# uk_ad.net
KiCad netlist of a schematic drawn in Altium Designer
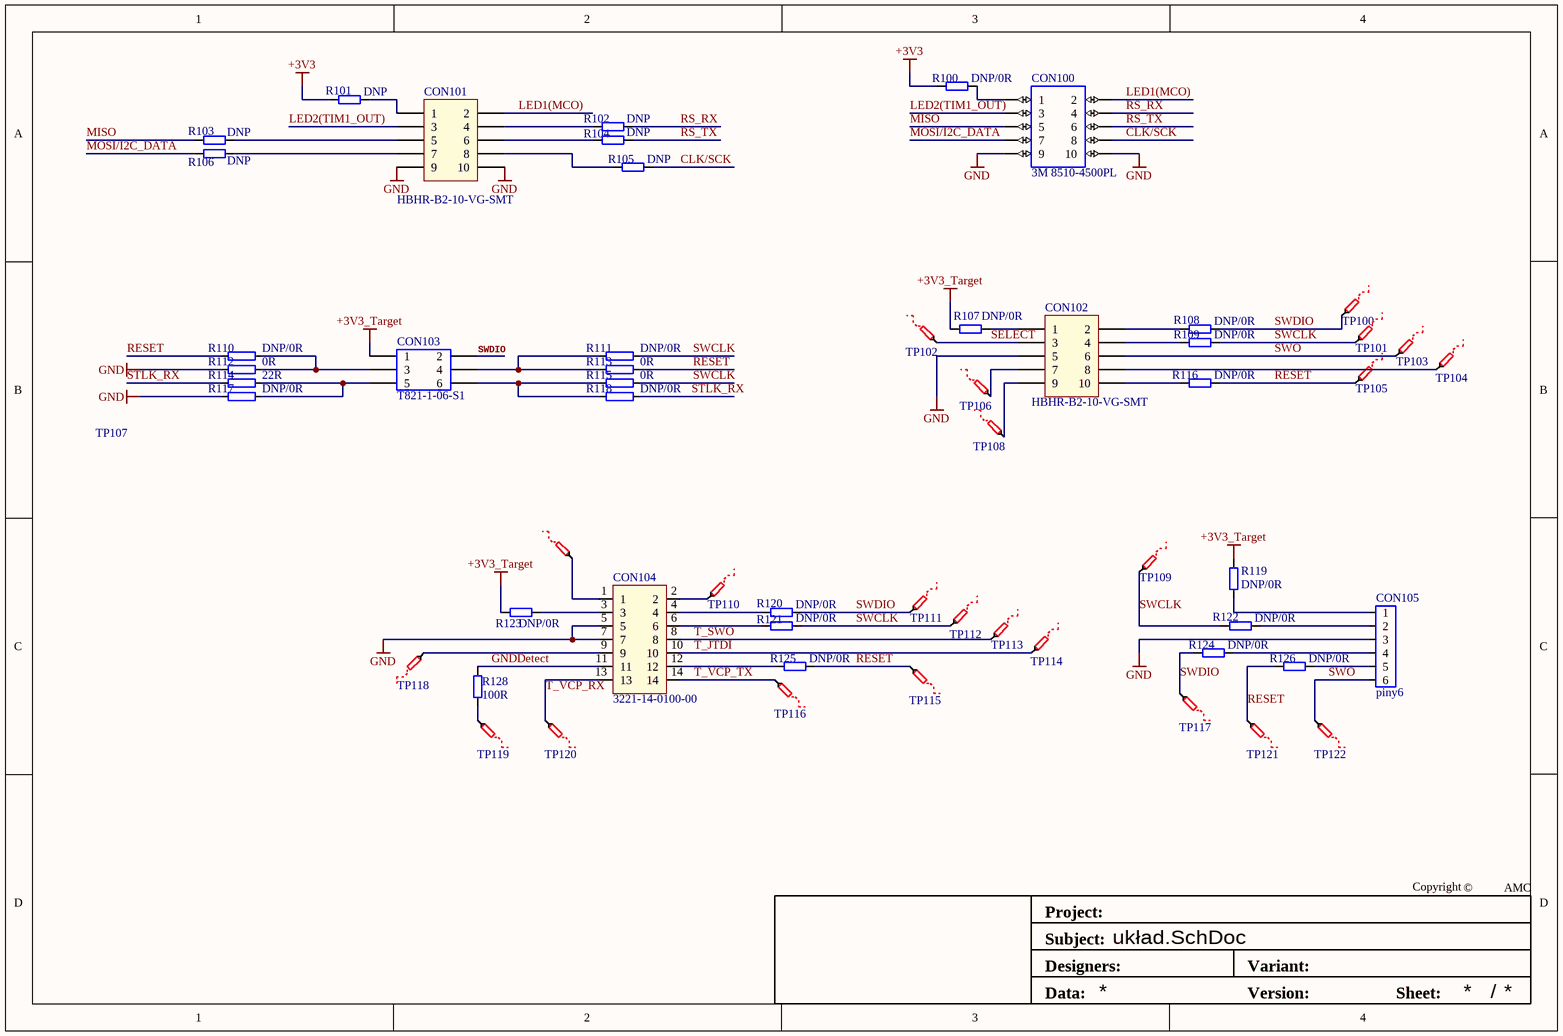
[diagram p0: układ.SchDoc]

(export (version "E")
  (design (tool "Eeschema 10.0.6"))
  (components
    (comp (ref "CON100")
      (value "3M 8510-4500PL")
      (footprint "PINY2X5 zenskie")
      (description "Gniazdo; IDC; żeńskie; PIN: 10; proste; THT; złocony; 3A; 2,54mm")
      (libsource (lib "ECS_AMC_all_2016") (part "piny_2x5 zenskie Petroster"))
    )
    (comp (ref "CON101")
      (value "HBHR-B2-10-VG-SMT")
      (footprint "piny_1k27_2x5_smd_IDC")
      (description "AMC Debug connector\r\nIDC 2x5 pitch 1.27")
      (libsource (lib "ECS_AMC_all_2016") (part "AMC_Debug"))
    )
    (comp (ref "CON102")
      (value "HBHR-B2-10-VG-SMT")
      (footprint "piny_1k27_2x5_smd_IDC")
      (description "AMC Debug connector\r\nIDC 2x5 pitch 1.27")
      (libsource (lib "ECS_AMC_all_2016") (part "AMC_Debug"))
    )
    (comp (ref "CON103")
      (value "T821-1-06-S1")
      (footprint "IDC_2X3_2.54MM")
      (libsource (lib "ECS_AMC_all_2016") (part "piny_2x3"))
    )
    (comp (ref "CON104")
      (value "3221-14-0100-00")
      (footprint "PINY_2X7_1.27_THT")
      (description "CONN HEADER VERT 14POS 1.27MM")
      (libsource (lib "ECS_AMC_all_2016") (part "3221-14-0100-00"))
    )
    (comp (ref "CON105")
      (value "piny6")
      (footprint "piny1x6")
      (libsource (lib "ECS_AMC_all_2016") (part "piny6"))
    )
    (comp (ref "R100") (value "DNP/0R") (footprint "0603") (libsource (lib "ECS_all_2014") (part "rez_3k")))
    (comp (ref "R101") (value "DNP") (footprint "0805") (libsource (lib "ECS_all_2014") (part "rez_3k")))
    (comp (ref "R102") (value "DNP") (footprint "0603") (libsource (lib "ECS_all_2014") (part "rez_3k")))
    (comp (ref "R103") (value "DNP") (footprint "0603") (libsource (lib "ECS_all_2014") (part "rez_3k")))
    (comp (ref "R104") (value "DNP") (footprint "0603") (libsource (lib "ECS_all_2014") (part "rez_3k")))
    (comp (ref "R105") (value "DNP") (footprint "0603") (libsource (lib "ECS_all_2014") (part "rez_3k")))
    (comp (ref "R106") (value "DNP") (footprint "0603") (libsource (lib "ECS_all_2014") (part "rez_3k")))
    (comp (ref "R107") (value "DNP/0R") (footprint "0603") (libsource (lib "ECS_all_2014") (part "rez_3k")))
    (comp (ref "R108") (value "DNP/0R") (footprint "0603") (libsource (lib "ECS_all_2014") (part "rez_3k")))
    (comp (ref "R109") (value "DNP/0R") (footprint "0603") (libsource (lib "ECS_all_2014") (part "rez_3k")))
    (comp (ref "R110") (value "DNP/0R") (footprint "0603") (libsource (lib "ECS_AMC_all_2016") (part "RES")))
    (comp (ref "R111") (value "DNP/0R") (footprint "0603") (libsource (lib "ECS_AMC_all_2016") (part "RES")))
    (comp (ref "R112") (value "0R") (footprint "0603") (libsource (lib "ECS_AMC_all_2016") (part "RES")))
    (comp (ref "R113") (value "0R") (footprint "0603") (libsource (lib "ECS_AMC_all_2016") (part "RES")))
    (comp (ref "R114") (value "22R") (footprint "0603") (libsource (lib "ECS_AMC_all_2016") (part "RES")))
    (comp (ref "R115") (value "0R") (footprint "0603") (libsource (lib "ECS_AMC_all_2016") (part "RES")))
    (comp (ref "R116") (value "DNP/0R") (footprint "0603") (libsource (lib "ECS_all_2014") (part "rez_3k")))
    (comp (ref "R117") (value "DNP/0R") (footprint "0603") (libsource (lib "ECS_AMC_all_2016") (part "RES")))
    (comp (ref "R118") (value "DNP/0R") (footprint "0603") (libsource (lib "ECS_AMC_all_2016") (part "RES")))
    (comp (ref "R119") (value "DNP/0R") (footprint "0603") (libsource (lib "") (part "rez_3k_2")))
    (comp (ref "R120") (value "DNP/0R") (footprint "0603") (libsource (lib "ECS_all_2014") (part "rez_3k")))
    (comp (ref "R121") (value "DNP/0R") (footprint "0603") (libsource (lib "ECS_all_2014") (part "rez_3k")))
    (comp (ref "R122") (value "DNP/0R") (footprint "0603") (libsource (lib "ECS_all_2014") (part "rez_3k")))
    (comp (ref "R123") (value "DNP/0R") (footprint "0603") (libsource (lib "") (part "rez_3k_1")))
    (comp (ref "R124") (value "DNP/0R") (footprint "0603") (libsource (lib "ECS_all_2014") (part "rez_3k")))
    (comp (ref "R125") (value "DNP/0R") (footprint "0603") (libsource (lib "ECS_all_2014") (part "rez_3k")))
    (comp (ref "R126") (value "DNP/0R") (footprint "0603") (libsource (lib "ECS_all_2014") (part "rez_3k")))
    (comp (ref "R128") (value "100R") (footprint "0603") (libsource (lib "") (part "rez_3k_2")))
    (comp (ref "TP100")
      (value "testpoint")
      (footprint "testpoint_50mils_octagonal")
      (description "Testpoint")
      (libsource (lib "ECS_AMC_all_2016") (part "testpoint"))
    )
    (comp (ref "TP101")
      (value "testpoint")
      (footprint "testpoint_50mils_octagonal")
      (description "Testpoint")
      (libsource (lib "ECS_AMC_all_2016") (part "testpoint"))
    )
    (comp (ref "TP102")
      (value "testpoint")
      (footprint "testpoint_50mils_octagonal")
      (description "Testpoint")
      (libsource (lib "ECS_AMC_all_2016") (part "testpoint"))
    )
    (comp (ref "TP103")
      (value "testpoint")
      (footprint "testpoint_50mils_octagonal")
      (description "Testpoint")
      (libsource (lib "ECS_AMC_all_2016") (part "testpoint"))
    )
    (comp (ref "TP104")
      (value "testpoint")
      (footprint "testpoint_50mils_octagonal")
      (description "Testpoint")
      (libsource (lib "ECS_AMC_all_2016") (part "testpoint"))
    )
    (comp (ref "TP105")
      (value "testpoint")
      (footprint "testpoint_50mils_octagonal")
      (description "Testpoint")
      (libsource (lib "ECS_AMC_all_2016") (part "testpoint"))
    )
    (comp (ref "TP106")
      (value "testpoint")
      (footprint "testpoint_50mils_octagonal")
      (description "Testpoint")
      (libsource (lib "ECS_AMC_all_2016") (part "testpoint"))
    )
    (comp (ref "TP107")
      (value "testpoint")
      (footprint "testpoint_50mils_octagonal")
      (description "Testpoint")
      (libsource (lib "ECS_AMC_all_2016") (part "testpoint"))
    )
    (comp (ref "TP108")
      (value "testpoint")
      (footprint "testpoint_50mils_octagonal")
      (description "Testpoint")
      (libsource (lib "ECS_AMC_all_2016") (part "testpoint"))
    )
    (comp (ref "TP109")
      (value "testpoint")
      (footprint "testpoint_50mils_octagonal")
      (description "Testpoint")
      (libsource (lib "ECS_AMC_all_2016") (part "testpoint"))
    )
    (comp (ref "TP110")
      (value "testpoint")
      (footprint "testpoint_50mils_octagonal")
      (description "Testpoint")
      (libsource (lib "ECS_AMC_all_2016") (part "testpoint"))
    )
    (comp (ref "TP111")
      (value "testpoint")
      (footprint "testpoint_50mils_octagonal")
      (description "Testpoint")
      (libsource (lib "ECS_AMC_all_2016") (part "testpoint"))
    )
    (comp (ref "TP112")
      (value "testpoint")
      (footprint "testpoint_50mils_octagonal")
      (description "Testpoint")
      (libsource (lib "ECS_AMC_all_2016") (part "testpoint"))
    )
    (comp (ref "TP113")
      (value "testpoint")
      (footprint "testpoint_50mils_octagonal")
      (description "Testpoint")
      (libsource (lib "ECS_AMC_all_2016") (part "testpoint"))
    )
    (comp (ref "TP114")
      (value "testpoint")
      (footprint "testpoint_50mils_octagonal")
      (description "Testpoint")
      (libsource (lib "ECS_AMC_all_2016") (part "testpoint"))
    )
    (comp (ref "TP115")
      (value "testpoint")
      (footprint "testpoint_50mils_octagonal")
      (description "Testpoint")
      (libsource (lib "ECS_AMC_all_2016") (part "testpoint"))
    )
    (comp (ref "TP116")
      (value "testpoint")
      (footprint "testpoint_50mils_octagonal")
      (description "Testpoint")
      (libsource (lib "ECS_AMC_all_2016") (part "testpoint"))
    )
    (comp (ref "TP117")
      (value "testpoint")
      (footprint "testpoint_50mils_octagonal")
      (description "Testpoint")
      (libsource (lib "ECS_AMC_all_2016") (part "testpoint"))
    )
    (comp (ref "TP118")
      (value "testpoint")
      (footprint "testpoint_50mils_octagonal")
      (description "Testpoint")
      (libsource (lib "ECS_AMC_all_2016") (part "testpoint"))
    )
    (comp (ref "TP119")
      (value "testpoint")
      (footprint "testpoint_50mils_octagonal")
      (description "Testpoint")
      (libsource (lib "ECS_AMC_all_2016") (part "testpoint"))
    )
    (comp (ref "TP120")
      (value "testpoint")
      (footprint "testpoint_50mils_octagonal")
      (description "Testpoint")
      (libsource (lib "ECS_AMC_all_2016") (part "testpoint"))
    )
    (comp (ref "TP121")
      (value "testpoint")
      (footprint "testpoint_50mils_octagonal")
      (description "Testpoint")
      (libsource (lib "ECS_AMC_all_2016") (part "testpoint"))
    )
    (comp (ref "TP122")
      (value "testpoint")
      (footprint "testpoint_50mils_octagonal")
      (description "Testpoint")
      (libsource (lib "ECS_AMC_all_2016") (part "testpoint"))
    )
  )
  (nets
    (net (code "1") (name "+3V3") (class "Default")
      (node (ref "R100") (pin "1") (pinfunction "1_1") (pintype "passive"))
      (node (ref "R101") (pin "1") (pinfunction "1_1") (pintype "passive"))
    )
    (net (code "2") (name "+3V3_Target") (class "Default")
      (node (ref "CON103") (pin "1") (pinfunction "1_1") (pintype "passive"))
      (node (ref "R107") (pin "1") (pinfunction "1_1") (pintype "passive"))
      (node (ref "R119") (pin "2") (pinfunction "2_2") (pintype "passive"))
      (node (ref "R123") (pin "2") (pinfunction "2_2") (pintype "passive"))
    )
    (net (code "3") (name "/CLK{slash}SCK") (class "Default")
      (node (ref "CON100") (pin "8") (pinfunction "8_8") (pintype "bidirectional"))
      (node (ref "R105") (pin "2") (pinfunction "2_2") (pintype "passive"))
    )
    (net (code "4") (name "/GNDDetect") (class "Default")
      (node (ref "CON104") (pin "11") (pinfunction "11_11") (pintype "passive"))
      (node (ref "R128") (pin "2") (pinfunction "2_2") (pintype "passive"))
    )
    (net (code "5") (name "/LED1(MCO)") (class "Default")
      (node (ref "CON100") (pin "2") (pinfunction "2_2") (pintype "bidirectional"))
      (node (ref "CON101") (pin "2") (pinfunction "2_2") (pintype "passive"))
    )
    (net (code "6") (name "/LED2(TIM1_OUT)") (class "Default")
      (node (ref "CON100") (pin "3") (pinfunction "3_3") (pintype "bidirectional"))
      (node (ref "CON101") (pin "3") (pinfunction "3_3") (pintype "passive"))
    )
    (net (code "7") (name "/MISO") (class "Default")
      (node (ref "CON100") (pin "5") (pinfunction "5_5") (pintype "bidirectional"))
      (node (ref "R103") (pin "1") (pinfunction "1_1") (pintype "passive"))
    )
    (net (code "8") (name "/MOSI{slash}I2C_DATA") (class "Default")
      (node (ref "CON100") (pin "7") (pinfunction "7_7") (pintype "bidirectional"))
      (node (ref "R106") (pin "1") (pinfunction "1_1") (pintype "passive"))
    )
    (net (code "9") (name "/RESET") (class "Default")
      (node (ref "R110") (pin "2") (pinfunction "2_2") (pintype "passive"))
      (node (ref "R113") (pin "1") (pinfunction "1_1") (pintype "passive"))
      (node (ref "R116") (pin "2") (pinfunction "2_2") (pintype "passive"))
      (node (ref "R125") (pin "2") (pinfunction "2_2") (pintype "passive"))
      (node (ref "R126") (pin "1") (pinfunction "1_1") (pintype "passive"))
      (node (ref "TP105") (pin "1") (pinfunction "1_1") (pintype "passive"))
      (node (ref "TP115") (pin "1") (pinfunction "1_1") (pintype "passive"))
      (node (ref "TP121") (pin "1") (pinfunction "1_1") (pintype "passive"))
    )
    (net (code "10") (name "/RS_RX") (class "Default")
      (node (ref "CON100") (pin "4") (pinfunction "4_4") (pintype "bidirectional"))
      (node (ref "R102") (pin "2") (pinfunction "2_2") (pintype "passive"))
    )
    (net (code "11") (name "/RS_TX") (class "Default")
      (node (ref "CON100") (pin "6") (pinfunction "6_6") (pintype "bidirectional"))
      (node (ref "R104") (pin "2") (pinfunction "2_2") (pintype "passive"))
    )
    (net (code "12") (name "/SELECT") (class "Default")
      (node (ref "CON102") (pin "3") (pinfunction "3_3") (pintype "passive"))
      (node (ref "TP102") (pin "1") (pinfunction "1_1") (pintype "passive"))
    )
    (net (code "13") (name "/STLK_RX") (class "Default")
      (node (ref "R114") (pin "2") (pinfunction "2_2") (pintype "passive"))
      (node (ref "R118") (pin "1") (pinfunction "1_1") (pintype "passive"))
    )
    (net (code "14") (name "/SWCLK") (class "Default")
      (node (ref "R109") (pin "2") (pinfunction "2_2") (pintype "passive"))
      (node (ref "R111") (pin "1") (pinfunction "1_1") (pintype "passive"))
      (node (ref "R115") (pin "1") (pinfunction "1_1") (pintype "passive"))
      (node (ref "R121") (pin "2") (pinfunction "2_2") (pintype "passive"))
      (node (ref "R122") (pin "1") (pinfunction "1_1") (pintype "passive"))
      (node (ref "TP101") (pin "1") (pinfunction "1_1") (pintype "passive"))
      (node (ref "TP109") (pin "1") (pinfunction "1_1") (pintype "passive"))
      (node (ref "TP112") (pin "1") (pinfunction "1_1") (pintype "passive"))
    )
    (net (code "15") (name "/SWDIO") (class "Default")
      (node (ref "CON103") (pin "2") (pinfunction "2_2") (pintype "passive"))
      (node (ref "R108") (pin "2") (pinfunction "2_2") (pintype "passive"))
      (node (ref "R120") (pin "2") (pinfunction "2_2") (pintype "passive"))
      (node (ref "R124") (pin "1") (pinfunction "1_1") (pintype "passive"))
      (node (ref "TP100") (pin "1") (pinfunction "1_1") (pintype "passive"))
      (node (ref "TP111") (pin "1") (pinfunction "1_1") (pintype "passive"))
      (node (ref "TP117") (pin "1") (pinfunction "1_1") (pintype "passive"))
    )
    (net (code "16") (name "/SWO") (class "Default")
      (node (ref "CON102") (pin "6") (pinfunction "6_6") (pintype "passive"))
      (node (ref "CON105") (pin "6") (pinfunction "6_6") (pintype "passive"))
      (node (ref "TP103") (pin "1") (pinfunction "1_1") (pintype "passive"))
      (node (ref "TP122") (pin "1") (pinfunction "1_1") (pintype "passive"))
    )
    (net (code "17") (name "/T_JTDI") (class "Default")
      (node (ref "CON104") (pin "10") (pinfunction "10_10") (pintype "passive"))
      (node (ref "TP114") (pin "1") (pinfunction "1_1") (pintype "passive"))
    )
    (net (code "18") (name "/T_SWO") (class "Default")
      (node (ref "CON104") (pin "8") (pinfunction "8_8") (pintype "passive"))
      (node (ref "TP113") (pin "1") (pinfunction "1_1") (pintype "passive"))
    )
    (net (code "19") (name "/T_VCP_RX") (class "Default")
      (node (ref "CON104") (pin "13") (pinfunction "13_13") (pintype "passive"))
      (node (ref "TP120") (pin "1") (pinfunction "1_1") (pintype "passive"))
    )
    (net (code "20") (name "/T_VCP_TX") (class "Default")
      (node (ref "CON104") (pin "14") (pinfunction "14_14") (pintype "passive"))
      (node (ref "TP116") (pin "1") (pinfunction "1_1") (pintype "passive"))
    )
    (net (code "21") (name "GND") (class "Default")
      (node (ref "CON100") (pin "10") (pinfunction "10_10") (pintype "bidirectional"))
      (node (ref "CON100") (pin "9") (pinfunction "9_9") (pintype "bidirectional"))
      (node (ref "CON101") (pin "10") (pinfunction "10_10") (pintype "passive"))
      (node (ref "CON101") (pin "9") (pinfunction "9_9") (pintype "passive"))
      (node (ref "CON102") (pin "5") (pinfunction "5_5") (pintype "passive"))
      (node (ref "CON104") (pin "5") (pinfunction "5_5") (pintype "passive"))
      (node (ref "CON104") (pin "7") (pinfunction "7_7") (pintype "passive"))
      (node (ref "CON105") (pin "3") (pinfunction "3_3") (pintype "passive"))
      (node (ref "R112") (pin "2") (pinfunction "2_2") (pintype "passive"))
      (node (ref "R117") (pin "2") (pinfunction "2_2") (pintype "passive"))
    )
    (net (code "22") (name "Net-(CON100-Pad1)") (class "Default")
      (node (ref "CON100") (pin "1") (pinfunction "1_1") (pintype "bidirectional"))
      (node (ref "R100") (pin "2") (pinfunction "2_2") (pintype "passive"))
    )
    (net (code "23") (name "Net-(CON101-Pad1)") (class "Default")
      (node (ref "CON101") (pin "1") (pinfunction "1_1") (pintype "passive"))
      (node (ref "R101") (pin "2") (pinfunction "2_2") (pintype "passive"))
    )
    (net (code "24") (name "Net-(CON101-Pad4)") (class "Default")
      (node (ref "CON101") (pin "4") (pinfunction "4_4") (pintype "passive"))
      (node (ref "R102") (pin "1") (pinfunction "1_1") (pintype "passive"))
    )
    (net (code "25") (name "Net-(CON101-Pad5)") (class "Default")
      (node (ref "CON101") (pin "5") (pinfunction "5_5") (pintype "passive"))
      (node (ref "R103") (pin "2") (pinfunction "2_2") (pintype "passive"))
    )
    (net (code "26") (name "Net-(CON101-Pad6)") (class "Default")
      (node (ref "CON101") (pin "6") (pinfunction "6_6") (pintype "passive"))
      (node (ref "R104") (pin "1") (pinfunction "1_1") (pintype "passive"))
    )
    (net (code "27") (name "Net-(CON101-Pad7)") (class "Default")
      (node (ref "CON101") (pin "7") (pinfunction "7_7") (pintype "passive"))
      (node (ref "R106") (pin "2") (pinfunction "2_2") (pintype "passive"))
    )
    (net (code "28") (name "Net-(CON101-Pad8)") (class "Default")
      (node (ref "CON101") (pin "8") (pinfunction "8_8") (pintype "passive"))
      (node (ref "R105") (pin "1") (pinfunction "1_1") (pintype "passive"))
    )
    (net (code "29") (name "Net-(CON102-Pad1)") (class "Default")
      (node (ref "CON102") (pin "1") (pinfunction "1_1") (pintype "passive"))
      (node (ref "R107") (pin "2") (pinfunction "2_2") (pintype "passive"))
    )
    (net (code "30") (name "Net-(CON102-Pad2)") (class "Default")
      (node (ref "CON102") (pin "2") (pinfunction "2_2") (pintype "passive"))
      (node (ref "R108") (pin "1") (pinfunction "1_1") (pintype "passive"))
    )
    (net (code "31") (name "Net-(CON102-Pad4)") (class "Default")
      (node (ref "CON102") (pin "4") (pinfunction "4_4") (pintype "passive"))
      (node (ref "R109") (pin "1") (pinfunction "1_1") (pintype "passive"))
    )
    (net (code "32") (name "Net-(CON102-Pad7)") (class "Default")
      (node (ref "CON102") (pin "7") (pinfunction "7_7") (pintype "passive"))
      (node (ref "TP106") (pin "1") (pinfunction "1_1") (pintype "passive"))
    )
    (net (code "33") (name "Net-(CON102-Pad8)") (class "Default")
      (node (ref "CON102") (pin "8") (pinfunction "8_8") (pintype "passive"))
      (node (ref "TP104") (pin "1") (pinfunction "1_1") (pintype "passive"))
    )
    (net (code "34") (name "Net-(CON102-Pad9)") (class "Default")
      (node (ref "CON102") (pin "9") (pinfunction "9_9") (pintype "passive"))
      (node (ref "TP108") (pin "1") (pinfunction "1_1") (pintype "passive"))
    )
    (net (code "35") (name "Net-(CON102-Pad10)") (class "Default")
      (node (ref "CON102") (pin "10") (pinfunction "10_10") (pintype "passive"))
      (node (ref "R116") (pin "1") (pinfunction "1_1") (pintype "passive"))
    )
    (net (code "36") (name "Net-(CON103-Pad3)") (class "Default")
      (node (ref "CON103") (pin "3") (pinfunction "3_3") (pintype "passive"))
      (node (ref "R110") (pin "1") (pinfunction "1_1") (pintype "passive"))
      (node (ref "R112") (pin "1") (pinfunction "1_1") (pintype "passive"))
    )
    (net (code "37") (name "Net-(CON103-Pad4)") (class "Default")
      (node (ref "CON103") (pin "4") (pinfunction "4_4") (pintype "passive"))
      (node (ref "R111") (pin "2") (pinfunction "2_2") (pintype "passive"))
      (node (ref "R113") (pin "2") (pinfunction "2_2") (pintype "passive"))
    )
    (net (code "38") (name "Net-(CON103-Pad5)") (class "Default")
      (node (ref "CON103") (pin "5") (pinfunction "5_5") (pintype "passive"))
      (node (ref "R114") (pin "1") (pinfunction "1_1") (pintype "passive"))
      (node (ref "R117") (pin "1") (pinfunction "1_1") (pintype "passive"))
    )
    (net (code "39") (name "Net-(CON103-Pad6)") (class "Default")
      (node (ref "CON103") (pin "6") (pinfunction "6_6") (pintype "passive"))
      (node (ref "R115") (pin "2") (pinfunction "2_2") (pintype "passive"))
      (node (ref "R118") (pin "2") (pinfunction "2_2") (pintype "passive"))
    )
    (net (code "40") (name "Net-(CON104-Pad1)") (class "Default")
      (node (ref "CON104") (pin "1") (pinfunction "1_1") (pintype "passive"))
      (node (ref "TP107") (pin "1") (pinfunction "1_1") (pintype "passive"))
    )
    (net (code "41") (name "Net-(CON104-Pad2)") (class "Default")
      (node (ref "CON104") (pin "2") (pinfunction "2_2") (pintype "passive"))
      (node (ref "TP110") (pin "1") (pinfunction "1_1") (pintype "passive"))
    )
    (net (code "42") (name "Net-(CON104-Pad3)") (class "Default")
      (node (ref "CON104") (pin "3") (pinfunction "3_3") (pintype "passive"))
      (node (ref "R123") (pin "1") (pinfunction "1_1") (pintype "passive"))
    )
    (net (code "43") (name "Net-(CON104-Pad4)") (class "Default")
      (node (ref "CON104") (pin "4") (pinfunction "4_4") (pintype "passive"))
      (node (ref "R120") (pin "1") (pinfunction "1_1") (pintype "passive"))
    )
    (net (code "44") (name "Net-(CON104-Pad6)") (class "Default")
      (node (ref "CON104") (pin "6") (pinfunction "6_6") (pintype "passive"))
      (node (ref "R121") (pin "1") (pinfunction "1_1") (pintype "passive"))
    )
    (net (code "45") (name "Net-(CON104-Pad9)") (class "Default")
      (node (ref "CON104") (pin "9") (pinfunction "9_9") (pintype "passive"))
      (node (ref "TP118") (pin "1") (pinfunction "1_1") (pintype "passive"))
    )
    (net (code "46") (name "Net-(CON104-Pad12)") (class "Default")
      (node (ref "CON104") (pin "12") (pinfunction "12_12") (pintype "passive"))
      (node (ref "R125") (pin "1") (pinfunction "1_1") (pintype "passive"))
    )
    (net (code "47") (name "Net-(CON105-Pad1)") (class "Default")
      (node (ref "CON105") (pin "1") (pinfunction "1_1") (pintype "passive"))
      (node (ref "R119") (pin "1") (pinfunction "1_1") (pintype "passive"))
    )
    (net (code "48") (name "Net-(CON105-Pad2)") (class "Default")
      (node (ref "CON105") (pin "2") (pinfunction "2_2") (pintype "passive"))
      (node (ref "R122") (pin "2") (pinfunction "2_2") (pintype "passive"))
    )
    (net (code "49") (name "Net-(CON105-Pad4)") (class "Default")
      (node (ref "CON105") (pin "4") (pinfunction "4_4") (pintype "passive"))
      (node (ref "R124") (pin "2") (pinfunction "2_2") (pintype "passive"))
    )
    (net (code "50") (name "Net-(CON105-Pad5)") (class "Default")
      (node (ref "CON105") (pin "5") (pinfunction "5_5") (pintype "passive"))
      (node (ref "R126") (pin "2") (pinfunction "2_2") (pintype "passive"))
    )
    (net (code "51") (name "Net-(R128-Pad1)") (class "Default")
      (node (ref "R128") (pin "1") (pinfunction "1_1") (pintype "passive"))
      (node (ref "TP119") (pin "1") (pinfunction "1_1") (pintype "passive"))
    )
  )
)
